# ESP8266_Single_RGB_RevA.net
KiCad netlist of a schematic drawn in EAGLE
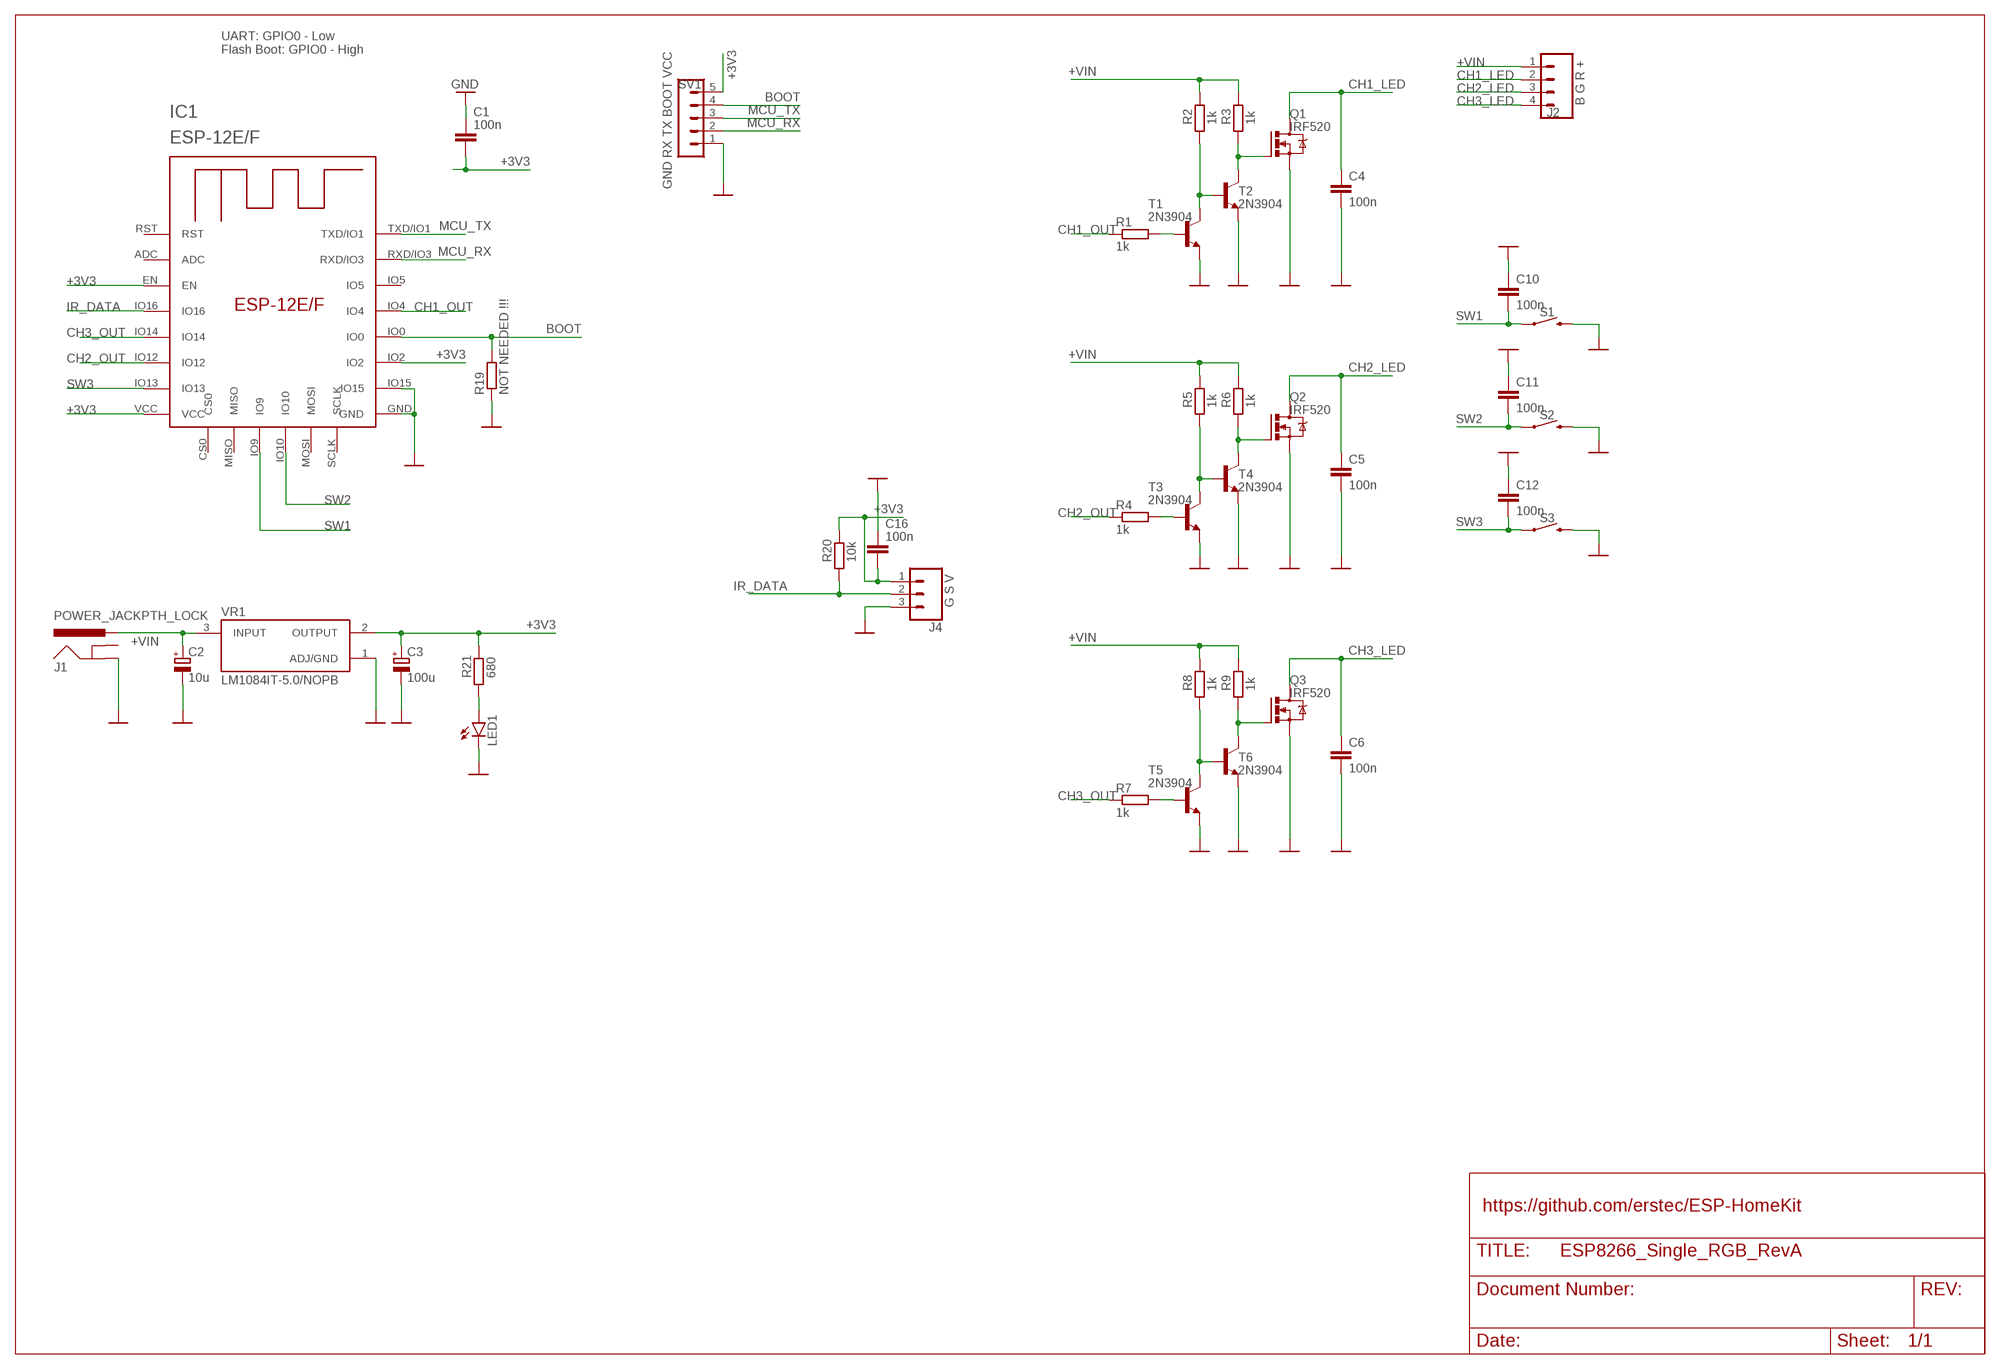
[diagram p0: schematic, sheet 1]

(export (version "E")
  (design (tool "Eeschema 10.0.6"))
  (components
    (comp (ref "C1")
      (value "100n")
      (footprint "eagle-import:C025-024X044")
      (libsource (lib "eagle-import") (part "C-EU025-024X044"))
    )
    (comp (ref "C2")
      (value "10u")
      (footprint "eagle-import:E2,5-6E")
      (libsource (lib "eagle-import") (part "CPOL-EUE2,5-6E"))
    )
    (comp (ref "C3")
      (value "100u")
      (footprint "eagle-import:E2,5-6")
      (libsource (lib "eagle-import") (part "CPOL-EUE2.5-6"))
    )
    (comp (ref "C4")
      (value "100n")
      (footprint "eagle-import:C025-024X044")
      (libsource (lib "eagle-import") (part "C-EU025-024X044"))
    )
    (comp (ref "C5")
      (value "100n")
      (footprint "eagle-import:C025-024X044")
      (libsource (lib "eagle-import") (part "C-EU025-024X044"))
    )
    (comp (ref "C6")
      (value "100n")
      (footprint "eagle-import:C025-024X044")
      (libsource (lib "eagle-import") (part "C-EU025-024X044"))
    )
    (comp (ref "C10")
      (value "100n")
      (footprint "eagle-import:C025-024X044")
      (libsource (lib "eagle-import") (part "C-EU025-024X044"))
    )
    (comp (ref "C11")
      (value "100n")
      (footprint "eagle-import:C025-024X044")
      (libsource (lib "eagle-import") (part "C-EU025-024X044"))
    )
    (comp (ref "C12")
      (value "100n")
      (footprint "eagle-import:C025-024X044")
      (libsource (lib "eagle-import") (part "C-EU025-024X044"))
    )
    (comp (ref "C16")
      (value "100n")
      (footprint "eagle-import:C025-024X044")
      (libsource (lib "eagle-import") (part "C-EU025-024X044"))
    )
    (comp (ref "IC1")
      (value "ESP-12E/F")
      (footprint "eagle-import:ESP-12E")
      (libsource (lib "eagle-import") (part "ESP-12E/F"))
    )
    (comp (ref "J1")
      (value "POWER_JACKPTH_LOCK")
      (footprint "eagle-import:POWER_JACK_PTH_LOCK")
      (libsource (lib "eagle-import") (part "POWER_JACKPTH_LOCK"))
    )
    (comp (ref "J2")
      (value "B G R +")
      (footprint "eagle-import:SCREWTERMINAL-3.5MM-4_LOCK")
      (libsource (lib "eagle-import") (part "CONN_04SCREW_LOCK"))
    )
    (comp (ref "J4")
      (value "G S V")
      (footprint "eagle-import:SCREWTERMINAL-3.5MM-3_LOCK.007S")
      (libsource (lib "eagle-import") (part "CONN_03SCREW_LOCK"))
    )
    (comp (ref "LED1")
      (value "LED5MM")
      (footprint "eagle-import:LED5MM")
      (libsource (lib "eagle-import") (part "LED5MM"))
    )
    (comp (ref "Q1")
      (value "IRF520")
      (footprint "eagle-import:TO220BV")
      (libsource (lib "eagle-import") (part "IRF520"))
    )
    (comp (ref "Q2")
      (value "IRF520")
      (footprint "eagle-import:TO220BV")
      (libsource (lib "eagle-import") (part "IRF520"))
    )
    (comp (ref "Q3")
      (value "IRF520")
      (footprint "eagle-import:TO220BV")
      (libsource (lib "eagle-import") (part "IRF520"))
    )
    (comp (ref "R1")
      (value "1k")
      (footprint "eagle-import:0207_10")
      (libsource (lib "eagle-import") (part "R-EU_0207/10"))
    )
    (comp (ref "R2")
      (value "1k")
      (footprint "eagle-import:0207_10")
      (libsource (lib "eagle-import") (part "R-EU_0207/10"))
    )
    (comp (ref "R3")
      (value "1k")
      (footprint "eagle-import:0207_10")
      (libsource (lib "eagle-import") (part "R-EU_0207/10"))
    )
    (comp (ref "R4")
      (value "1k")
      (footprint "eagle-import:0207_10")
      (libsource (lib "eagle-import") (part "R-EU_0207/10"))
    )
    (comp (ref "R5")
      (value "1k")
      (footprint "eagle-import:0207_10")
      (libsource (lib "eagle-import") (part "R-EU_0207/10"))
    )
    (comp (ref "R6")
      (value "1k")
      (footprint "eagle-import:0207_10")
      (libsource (lib "eagle-import") (part "R-EU_0207/10"))
    )
    (comp (ref "R7")
      (value "1k")
      (footprint "eagle-import:0207_10")
      (libsource (lib "eagle-import") (part "R-EU_0207/10"))
    )
    (comp (ref "R8")
      (value "1k")
      (footprint "eagle-import:0207_10")
      (libsource (lib "eagle-import") (part "R-EU_0207/10"))
    )
    (comp (ref "R9")
      (value "1k")
      (footprint "eagle-import:0207_10")
      (libsource (lib "eagle-import") (part "R-EU_0207/10"))
    )
    (comp (ref "R19")
      (value "NOT NEEDED !!!")
      (footprint "eagle-import:0207_10")
      (libsource (lib "eagle-import") (part "R-EU_0207/10"))
    )
    (comp (ref "R20")
      (value "10k")
      (footprint "eagle-import:0207_10")
      (libsource (lib "eagle-import") (part "R-EU_0207/10"))
    )
    (comp (ref "R21")
      (value "680")
      (footprint "eagle-import:0207_10")
      (libsource (lib "eagle-import") (part "R-EU_0207/10"))
    )
    (comp (ref "S1")
      (value "MOMENTARY-SWITCH-SPST-PTH-6.0MM")
      (footprint "eagle-import:TACTILE_SWITCH_PTH_6.0MM")
      (libsource (lib "eagle-import") (part "MOMENTARY-SWITCH-SPST-PTH-6.0MM"))
    )
    (comp (ref "S2")
      (value "MOMENTARY-SWITCH-SPST-PTH-6.0MM")
      (footprint "eagle-import:TACTILE_SWITCH_PTH_6.0MM")
      (libsource (lib "eagle-import") (part "MOMENTARY-SWITCH-SPST-PTH-6.0MM"))
    )
    (comp (ref "S3")
      (value "MOMENTARY-SWITCH-SPST-PTH-6.0MM")
      (footprint "eagle-import:TACTILE_SWITCH_PTH_6.0MM")
      (libsource (lib "eagle-import") (part "MOMENTARY-SWITCH-SPST-PTH-6.0MM"))
    )
    (comp (ref "SV1")
      (value "GND RX TX BOOT VCC")
      (footprint "eagle-import:MA05-1")
      (libsource (lib "eagle-import") (part "MA05-1"))
    )
    (comp (ref "T1")
      (value "2N3904")
      (footprint "eagle-import:TO92")
      (libsource (lib "eagle-import") (part "2N3904"))
    )
    (comp (ref "T2")
      (value "2N3904")
      (footprint "eagle-import:TO92")
      (libsource (lib "eagle-import") (part "2N3904"))
    )
    (comp (ref "T3")
      (value "2N3904")
      (footprint "eagle-import:TO92")
      (libsource (lib "eagle-import") (part "2N3904"))
    )
    (comp (ref "T4")
      (value "2N3904")
      (footprint "eagle-import:TO92")
      (libsource (lib "eagle-import") (part "2N3904"))
    )
    (comp (ref "T5")
      (value "2N3904")
      (footprint "eagle-import:TO92")
      (libsource (lib "eagle-import") (part "2N3904"))
    )
    (comp (ref "T6")
      (value "2N3904")
      (footprint "eagle-import:TO92")
      (libsource (lib "eagle-import") (part "2N3904"))
    )
    (comp (ref "VR1")
      (value "LM1084IT-5.0/NOPB")
      (footprint "eagle-import:TO254P1054X470X1955-3")
      (fields (field (name "MF") "Texas Instruments"))
      (libsource (lib "eagle-import") (part "LM1084IT-5.0/NOPB"))
    )
  )
  (nets
    (net (code "1") (name "/+3V3") (class "Default")
      (node (ref "C1") (pin "2") (pinfunction "2_2") (pintype "passive"))
      (node (ref "C16") (pin "2") (pinfunction "2_2") (pintype "passive"))
      (node (ref "C3") (pin "+") (pinfunction "+_+") (pintype "passive"))
      (node (ref "IC1") (pin "EN") (pinfunction "EN_EN") (pintype "bidirectional"))
      (node (ref "IC1") (pin "IO2") (pinfunction "IO2_IO2") (pintype "bidirectional"))
      (node (ref "IC1") (pin "VCC") (pinfunction "VCC_VCC") (pintype "power_in"))
      (node (ref "J4") (pin "1") (pinfunction "1_1") (pintype "passive"))
      (node (ref "R20") (pin "2") (pinfunction "2_2") (pintype "passive"))
      (node (ref "R21") (pin "2") (pinfunction "2_2") (pintype "passive"))
      (node (ref "SV1") (pin "5") (pinfunction "5_5") (pintype "passive"))
      (node (ref "VR1") (pin "2") (pinfunction "OUTPUT_2") (pintype "output"))
    )
    (net (code "2") (name "/+VIN") (class "Default")
      (node (ref "C2") (pin "+") (pinfunction "+_+") (pintype "passive"))
      (node (ref "J1") (pin "PWR") (pinfunction "PWR_PWR") (pintype "bidirectional"))
      (node (ref "J2") (pin "1") (pinfunction "1_1") (pintype "passive"))
      (node (ref "R2") (pin "2") (pinfunction "2_2") (pintype "passive"))
      (node (ref "R3") (pin "2") (pinfunction "2_2") (pintype "passive"))
      (node (ref "R5") (pin "2") (pinfunction "2_2") (pintype "passive"))
      (node (ref "R6") (pin "2") (pinfunction "2_2") (pintype "passive"))
      (node (ref "R8") (pin "2") (pinfunction "2_2") (pintype "passive"))
      (node (ref "R9") (pin "2") (pinfunction "2_2") (pintype "passive"))
      (node (ref "VR1") (pin "3") (pinfunction "INPUT_3") (pintype "input"))
    )
    (net (code "3") (name "/BOOT") (class "Default")
      (node (ref "IC1") (pin "IO0") (pinfunction "IO0_IO0") (pintype "bidirectional"))
      (node (ref "R19") (pin "2") (pinfunction "2_2") (pintype "passive"))
      (node (ref "SV1") (pin "4") (pinfunction "4_4") (pintype "passive"))
    )
    (net (code "4") (name "/CH1_LED") (class "Default")
      (node (ref "C4") (pin "1") (pinfunction "1_1") (pintype "passive"))
      (node (ref "J2") (pin "2") (pinfunction "2_2") (pintype "passive"))
      (node (ref "Q1") (pin "D") (pinfunction "D_D") (pintype "passive"))
    )
    (net (code "5") (name "/CH1_OUT") (class "Default")
      (node (ref "IC1") (pin "IO4") (pinfunction "IO4_IO4") (pintype "bidirectional"))
      (node (ref "R1") (pin "1") (pinfunction "1_1") (pintype "passive"))
    )
    (net (code "6") (name "/CH2_LED") (class "Default")
      (node (ref "C5") (pin "1") (pinfunction "1_1") (pintype "passive"))
      (node (ref "J2") (pin "3") (pinfunction "3_3") (pintype "passive"))
      (node (ref "Q2") (pin "D") (pinfunction "D_D") (pintype "passive"))
    )
    (net (code "7") (name "/CH2_OUT") (class "Default")
      (node (ref "IC1") (pin "IO12") (pinfunction "IO12_IO12") (pintype "bidirectional"))
      (node (ref "R4") (pin "1") (pinfunction "1_1") (pintype "passive"))
    )
    (net (code "8") (name "/CH3_LED") (class "Default")
      (node (ref "C6") (pin "1") (pinfunction "1_1") (pintype "passive"))
      (node (ref "J2") (pin "4") (pinfunction "4_4") (pintype "passive"))
      (node (ref "Q3") (pin "D") (pinfunction "D_D") (pintype "passive"))
    )
    (net (code "9") (name "/CH3_OUT") (class "Default")
      (node (ref "IC1") (pin "IO14") (pinfunction "IO14_IO14") (pintype "bidirectional"))
      (node (ref "R7") (pin "1") (pinfunction "1_1") (pintype "passive"))
    )
    (net (code "10") (name "/IR_DATA") (class "Default")
      (node (ref "IC1") (pin "IO16") (pinfunction "IO16_IO16") (pintype "bidirectional"))
      (node (ref "J4") (pin "2") (pinfunction "2_2") (pintype "passive"))
      (node (ref "R20") (pin "1") (pinfunction "1_1") (pintype "passive"))
    )
    (net (code "11") (name "/MCU_RX") (class "Default")
      (node (ref "IC1") (pin "RXD/IO3") (pinfunction "RXD/IO3_RXD/IO3") (pintype "bidirectional"))
      (node (ref "SV1") (pin "2") (pinfunction "2_2") (pintype "passive"))
    )
    (net (code "12") (name "/MCU_TX") (class "Default")
      (node (ref "IC1") (pin "TXD/IO1") (pinfunction "TXD/IO1_TXD/IO1") (pintype "bidirectional"))
      (node (ref "SV1") (pin "3") (pinfunction "3_3") (pintype "passive"))
    )
    (net (code "13") (name "/SW1") (class "Default")
      (node (ref "C10") (pin "2") (pinfunction "2_2") (pintype "passive"))
      (node (ref "IC1") (pin "IO9") (pinfunction "IO9_IO9") (pintype "bidirectional"))
      (node (ref "S1") (pin "1") (pinfunction "1_1") (pintype "passive"))
    )
    (net (code "14") (name "/SW2") (class "Default")
      (node (ref "C11") (pin "2") (pinfunction "2_2") (pintype "passive"))
      (node (ref "IC1") (pin "IO10") (pinfunction "IO10_IO10") (pintype "bidirectional"))
      (node (ref "S2") (pin "1") (pinfunction "1_1") (pintype "passive"))
    )
    (net (code "15") (name "/SW3") (class "Default")
      (node (ref "C12") (pin "2") (pinfunction "2_2") (pintype "passive"))
      (node (ref "IC1") (pin "IO13") (pinfunction "IO13_IO13") (pintype "bidirectional"))
      (node (ref "S3") (pin "1") (pinfunction "1_1") (pintype "passive"))
    )
    (net (code "16") (name "GND") (class "Default")
      (node (ref "C1") (pin "1") (pinfunction "1_1") (pintype "passive"))
      (node (ref "C10") (pin "1") (pinfunction "1_1") (pintype "passive"))
      (node (ref "C11") (pin "1") (pinfunction "1_1") (pintype "passive"))
      (node (ref "C12") (pin "1") (pinfunction "1_1") (pintype "passive"))
      (node (ref "C16") (pin "1") (pinfunction "1_1") (pintype "passive"))
      (node (ref "C2") (pin "-") (pinfunction "-_-") (pintype "passive"))
      (node (ref "C3") (pin "-") (pinfunction "-_-") (pintype "passive"))
      (node (ref "C4") (pin "2") (pinfunction "2_2") (pintype "passive"))
      (node (ref "C5") (pin "2") (pinfunction "2_2") (pintype "passive"))
      (node (ref "C6") (pin "2") (pinfunction "2_2") (pintype "passive"))
      (node (ref "IC1") (pin "GND") (pinfunction "GND_GND") (pintype "power_in"))
      (node (ref "IC1") (pin "IO15") (pinfunction "IO15_IO15") (pintype "bidirectional"))
      (node (ref "J1") (pin "GND") (pinfunction "GND_GND") (pintype "bidirectional"))
      (node (ref "J4") (pin "3") (pinfunction "3_3") (pintype "passive"))
      (node (ref "LED1") (pin "K") (pinfunction "C_K") (pintype "passive"))
      (node (ref "Q1") (pin "S") (pinfunction "S_S") (pintype "passive"))
      (node (ref "Q2") (pin "S") (pinfunction "S_S") (pintype "passive"))
      (node (ref "Q3") (pin "S") (pinfunction "S_S") (pintype "passive"))
      (node (ref "R19") (pin "1") (pinfunction "1_1") (pintype "passive"))
      (node (ref "S1") (pin "3") (pinfunction "2_3") (pintype "passive"))
      (node (ref "S2") (pin "3") (pinfunction "2_3") (pintype "passive"))
      (node (ref "S3") (pin "3") (pinfunction "2_3") (pintype "passive"))
      (node (ref "SV1") (pin "1") (pinfunction "1_1") (pintype "passive"))
      (node (ref "T1") (pin "3") (pinfunction "E_3") (pintype "passive"))
      (node (ref "T2") (pin "3") (pinfunction "E_3") (pintype "passive"))
      (node (ref "T3") (pin "3") (pinfunction "E_3") (pintype "passive"))
      (node (ref "T4") (pin "3") (pinfunction "E_3") (pintype "passive"))
      (node (ref "T5") (pin "3") (pinfunction "E_3") (pintype "passive"))
      (node (ref "T6") (pin "3") (pinfunction "E_3") (pintype "passive"))
      (node (ref "VR1") (pin "1") (pinfunction "ADJ/GND_1") (pintype "power_in"))
    )
    (net (code "17") (name "Net-(LED1-PadA)") (class "Default")
      (node (ref "LED1") (pin "A") (pinfunction "A_A") (pintype "passive"))
      (node (ref "R21") (pin "1") (pinfunction "1_1") (pintype "passive"))
    )
    (net (code "18") (name "Net-(T1-B)") (class "Default")
      (node (ref "R1") (pin "2") (pinfunction "2_2") (pintype "passive"))
      (node (ref "T1") (pin "2") (pinfunction "B_2") (pintype "passive"))
    )
    (net (code "19") (name "Net-(T1-C)") (class "Default")
      (node (ref "R2") (pin "1") (pinfunction "1_1") (pintype "passive"))
      (node (ref "T1") (pin "1") (pinfunction "C_1") (pintype "passive"))
      (node (ref "T2") (pin "2") (pinfunction "B_2") (pintype "passive"))
    )
    (net (code "20") (name "Net-(T2-C)") (class "Default")
      (node (ref "Q1") (pin "G") (pinfunction "G_G") (pintype "passive"))
      (node (ref "R3") (pin "1") (pinfunction "1_1") (pintype "passive"))
      (node (ref "T2") (pin "1") (pinfunction "C_1") (pintype "passive"))
    )
    (net (code "21") (name "Net-(T3-B)") (class "Default")
      (node (ref "R4") (pin "2") (pinfunction "2_2") (pintype "passive"))
      (node (ref "T3") (pin "2") (pinfunction "B_2") (pintype "passive"))
    )
    (net (code "22") (name "Net-(T3-C)") (class "Default")
      (node (ref "R5") (pin "1") (pinfunction "1_1") (pintype "passive"))
      (node (ref "T3") (pin "1") (pinfunction "C_1") (pintype "passive"))
      (node (ref "T4") (pin "2") (pinfunction "B_2") (pintype "passive"))
    )
    (net (code "23") (name "Net-(T4-C)") (class "Default")
      (node (ref "Q2") (pin "G") (pinfunction "G_G") (pintype "passive"))
      (node (ref "R6") (pin "1") (pinfunction "1_1") (pintype "passive"))
      (node (ref "T4") (pin "1") (pinfunction "C_1") (pintype "passive"))
    )
    (net (code "24") (name "Net-(T5-B)") (class "Default")
      (node (ref "R7") (pin "2") (pinfunction "2_2") (pintype "passive"))
      (node (ref "T5") (pin "2") (pinfunction "B_2") (pintype "passive"))
    )
    (net (code "25") (name "Net-(T5-C)") (class "Default")
      (node (ref "R8") (pin "1") (pinfunction "1_1") (pintype "passive"))
      (node (ref "T5") (pin "1") (pinfunction "C_1") (pintype "passive"))
      (node (ref "T6") (pin "2") (pinfunction "B_2") (pintype "passive"))
    )
    (net (code "26") (name "Net-(T6-C)") (class "Default")
      (node (ref "Q3") (pin "G") (pinfunction "G_G") (pintype "passive"))
      (node (ref "R9") (pin "1") (pinfunction "1_1") (pintype "passive"))
      (node (ref "T6") (pin "1") (pinfunction "C_1") (pintype "passive"))
    )
    (net (code "27") (name "unconnected-(IC1-PadADC)") (class "Default")
      (node (ref "IC1") (pin "ADC") (pinfunction "ADC_ADC") (pintype "bidirectional"))
    )
    (net (code "28") (name "unconnected-(IC1-PadCS0)") (class "Default")
      (node (ref "IC1") (pin "CS0") (pinfunction "CS0_CS0") (pintype "bidirectional"))
    )
    (net (code "29") (name "unconnected-(IC1-PadIO5)") (class "Default")
      (node (ref "IC1") (pin "IO5") (pinfunction "IO5_IO5") (pintype "bidirectional"))
    )
    (net (code "30") (name "unconnected-(IC1-PadMISO)") (class "Default")
      (node (ref "IC1") (pin "MISO") (pinfunction "MISO_MISO") (pintype "bidirectional"))
    )
    (net (code "31") (name "unconnected-(IC1-PadMOSI)") (class "Default")
      (node (ref "IC1") (pin "MOSI") (pinfunction "MOSI_MOSI") (pintype "bidirectional"))
    )
    (net (code "32") (name "unconnected-(IC1-PadRST)") (class "Default")
      (node (ref "IC1") (pin "RST") (pinfunction "RST_RST") (pintype "input"))
    )
    (net (code "33") (name "unconnected-(IC1-PadSCLK)") (class "Default")
      (node (ref "IC1") (pin "SCLK") (pinfunction "SCLK_SCLK") (pintype "bidirectional"))
    )
    (net (code "34") (name "unconnected-(J1-PadGNDBREAK)") (class "Default")
      (node (ref "J1") (pin "GNDBREAK") (pinfunction "GNDBREAK_GNDBREAK") (pintype "bidirectional"))
    )
  )
)
